# Output_eFuse.net
KiCad netlist of a schematic drawn in Altium Designer
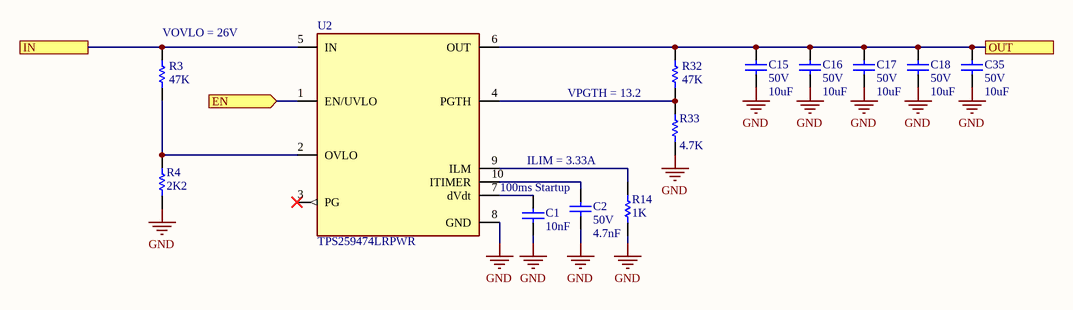
[diagram p0: Output_eFuse.SchDoc]

(export (version "E")
  (design (tool "Eeschema 10.0.6"))
  (components
    (comp (ref "C1")
      (value "CL21B103KBANNNC")
      (footprint "CAPC0805X060")
      (description "10nF ±10% 50V Ceramic Capacitor X7R 0805 (2012 Metric)")
      (fields
        (field (name "DISTRIBUTOR PART NUMBER") "C1710")
        (field (name "TOLERANCE") "10%")
        (field (name "CAPACITANCE") "10nF")
      )
      (libsource (lib "Ahristi_Library") (part "CL21B103KBANNNC"))
    )
    (comp (ref "C2")
      (value "0805B472K500NT")
      (footprint "CAPC0805X060")
      (description "4.7nF 50V X7R ±10% 0805 Multilayer Ceramic Capacitors MLCC - SMD/SMT ROHS")
      (fields
        (field (name "DISTRIBUTOR PART NUMBER") "C1744")
        (field (name "TOLERANCE") "10%")
        (field (name "VOLTAGE RATING") "50V")
        (field (name "CAPACITANCE") "4.7nF")
      )
      (libsource (lib "Ahristi_Library") (part "0805B472K500NT"))
    )
    (comp (ref "C15")
      (value "CL32B106KBJNNNE")
      (footprint "CAPC1210X090")
      (description "10 µF ±10% 50V Ceramic Capacitor X7R 1210 (3225 Metric)")
      (fields
        (field (name "DISTRIBUTOR PART NUMBER") "C138687")
        (field (name "TOLERANCE") "10%")
        (field (name "VOLTAGE RATING") "50V")
        (field (name "CAPACITANCE") "10uF")
      )
      (libsource (lib "Ahristi_Library") (part "CL32B106KBJNNNE"))
    )
    (comp (ref "C16")
      (value "CL32B106KBJNNNE")
      (footprint "CAPC1210X090")
      (description "10 µF ±10% 50V Ceramic Capacitor X7R 1210 (3225 Metric)")
      (fields
        (field (name "DISTRIBUTOR PART NUMBER") "C138687")
        (field (name "TOLERANCE") "10%")
        (field (name "VOLTAGE RATING") "50V")
        (field (name "CAPACITANCE") "10uF")
      )
      (libsource (lib "Ahristi_Library") (part "CL32B106KBJNNNE"))
    )
    (comp (ref "C17")
      (value "CL32B106KBJNNNE")
      (footprint "CAPC1210X090")
      (description "10 µF ±10% 50V Ceramic Capacitor X7R 1210 (3225 Metric)")
      (fields
        (field (name "DISTRIBUTOR PART NUMBER") "C138687")
        (field (name "TOLERANCE") "10%")
        (field (name "VOLTAGE RATING") "50V")
        (field (name "CAPACITANCE") "10uF")
      )
      (libsource (lib "Ahristi_Library") (part "CL32B106KBJNNNE"))
    )
    (comp (ref "C18")
      (value "CL32B106KBJNNNE")
      (footprint "CAPC1210X090")
      (description "10 µF ±10% 50V Ceramic Capacitor X7R 1210 (3225 Metric)")
      (fields
        (field (name "DISTRIBUTOR PART NUMBER") "C138687")
        (field (name "TOLERANCE") "10%")
        (field (name "VOLTAGE RATING") "50V")
        (field (name "CAPACITANCE") "10uF")
      )
      (libsource (lib "Ahristi_Library") (part "CL32B106KBJNNNE"))
    )
    (comp (ref "C35")
      (value "CL32B106KBJNNNE")
      (footprint "CAPC1210X090")
      (description "10 µF ±10% 50V Ceramic Capacitor X7R 1210 (3225 Metric)")
      (fields
        (field (name "DISTRIBUTOR PART NUMBER") "C138687")
        (field (name "TOLERANCE") "10%")
        (field (name "VOLTAGE RATING") "50V")
        (field (name "CAPACITANCE") "10uF")
      )
      (libsource (lib "Ahristi_Library") (part "CL32B106KBJNNNE"))
    )
    (comp (ref "R3")
      (value "0603WAF4702T5E")
      (footprint "RESC0603")
      (description "47kOhms 75V Thick Film Resistor ±1% ±100ppm/℃ 0603 Chip Resistor - Surface Mount ROHS")
      (fields
        (field (name "TOLERANCE") "1%")
        (field (name "DISTRIBUTOR PART NUMBER") "C25819")
        (field (name "RESISTANCE") "47K")
      )
      (libsource (lib "Ahristi_Library") (part "0603WAF4702T5E"))
    )
    (comp (ref "R4")
      (value "0603WAF2201T5E")
      (footprint "RESC0603")
      (description "2.2kOhms 75V Thick Film Resistor ±1% ±100ppm/℃ 0603 Chip Resistor - Surface Mount ROHS")
      (fields
        (field (name "TOLERANCE") "1%")
        (field (name "DISTRIBUTOR PART NUMBER") "C4190")
        (field (name "RESISTANCE") "2K2")
      )
      (libsource (lib "Ahristi_Library") (part "0603WAF2201T5E"))
    )
    (comp (ref "R14")
      (value "0603WAF1001T5E")
      (footprint "RESC0603")
      (description "1 kOhms 75V Thick Film Resistor ±1% ±100ppm/℃ 0603 Chip Resistor - Surface Mount ROHS")
      (fields
        (field (name "TOLERANCE") "1%")
        (field (name "DISTRIBUTOR PART NUMBER") "C21190")
        (field (name "RESISTANCE") "1K")
      )
      (libsource (lib "Ahristi_Library") (part "0603WAF1001T5E"))
    )
    (comp (ref "R32")
      (value "0603WAF4702T5E")
      (footprint "RESC0603")
      (description "47kOhms 75V Thick Film Resistor ±1% ±100ppm/℃ 0603 Chip Resistor - Surface Mount ROHS")
      (fields
        (field (name "TOLERANCE") "1%")
        (field (name "DISTRIBUTOR PART NUMBER") "C25819")
        (field (name "RESISTANCE") "47K")
      )
      (libsource (lib "Ahristi_Library") (part "0603WAF4702T5E"))
    )
    (comp (ref "R33")
      (value "0603WAF4701T5E")
      (footprint "RESC0603")
      (description "4.7 kOhms 75V Thick Film Resistor ±1% ±100ppm/℃ 0603 Chip Resistor - Surface Mount ROHS")
      (fields
        (field (name "TOLERANCE") "1%")
        (field (name "DISTRIBUTOR PART NUMBER") "C23162")
        (field (name "RESISTANCE") "4.7K")
      )
      (libsource (lib "Ahristi_Library") (part "0603WAF4701T5E"))
    )
    (comp (ref "U2")
      (value "TPS259474LRPWR")
      (footprint "VFQFN-10")
      (description "eFuse 5.5A, 2.7V~23V, 28mOhm, Reverse Current Blocking with Input Reverse Polarity Protection")
      (fields (field (name "DISTRIBUTOR PART NUMBER") "C2864845"))
      (libsource (lib "Ahristi_Library") (part "TPS259474LRPWR"))
    )
  )
  (nets
    (net (code "1") (name "/EN") (class "Default")
      (node (ref "U2") (pin "1") (pinfunction "EN/UVLO_1") (pintype "passive"))
    )
    (net (code "2") (name "/IN") (class "Default")
      (node (ref "R3") (pin "2") (pinfunction "2_2") (pintype "passive"))
      (node (ref "U2") (pin "5") (pinfunction "IN_5") (pintype "passive"))
    )
    (net (code "3") (name "/OUT") (class "Default")
      (node (ref "C15") (pin "2") (pinfunction "2_2") (pintype "passive"))
      (node (ref "C16") (pin "2") (pinfunction "2_2") (pintype "passive"))
      (node (ref "C17") (pin "2") (pinfunction "2_2") (pintype "passive"))
      (node (ref "C18") (pin "2") (pinfunction "2_2") (pintype "passive"))
      (node (ref "C35") (pin "2") (pinfunction "2_2") (pintype "passive"))
      (node (ref "R32") (pin "2") (pinfunction "2_2") (pintype "passive"))
      (node (ref "U2") (pin "6") (pinfunction "OUT_6") (pintype "passive"))
    )
    (net (code "4") (name "GND") (class "Default")
      (node (ref "C1") (pin "1") (pinfunction "1_1") (pintype "passive"))
      (node (ref "C15") (pin "1") (pinfunction "1_1") (pintype "passive"))
      (node (ref "C16") (pin "1") (pinfunction "1_1") (pintype "passive"))
      (node (ref "C17") (pin "1") (pinfunction "1_1") (pintype "passive"))
      (node (ref "C18") (pin "1") (pinfunction "1_1") (pintype "passive"))
      (node (ref "C2") (pin "1") (pinfunction "1_1") (pintype "passive"))
      (node (ref "C35") (pin "1") (pinfunction "1_1") (pintype "passive"))
      (node (ref "R14") (pin "1") (pinfunction "1_1") (pintype "passive"))
      (node (ref "R33") (pin "1") (pinfunction "1_1") (pintype "passive"))
      (node (ref "R4") (pin "1") (pinfunction "1_1") (pintype "passive"))
      (node (ref "U2") (pin "8") (pinfunction "GND_8") (pintype "passive"))
    )
    (net (code "5") (name "Net-(U2-ILM)") (class "Default")
      (node (ref "R14") (pin "2") (pinfunction "2_2") (pintype "passive"))
      (node (ref "U2") (pin "9") (pinfunction "ILM_9") (pintype "passive"))
    )
    (net (code "6") (name "Net-(U2-ITIMER)") (class "Default")
      (node (ref "C2") (pin "2") (pinfunction "2_2") (pintype "passive"))
      (node (ref "U2") (pin "10") (pinfunction "ITIMER_10") (pintype "passive"))
    )
    (net (code "7") (name "Net-(U2-OVLO)") (class "Default")
      (node (ref "R3") (pin "1") (pinfunction "1_1") (pintype "passive"))
      (node (ref "R4") (pin "2") (pinfunction "2_2") (pintype "passive"))
      (node (ref "U2") (pin "2") (pinfunction "OVLO_2") (pintype "passive"))
    )
    (net (code "8") (name "Net-(U2-PGTH)") (class "Default")
      (node (ref "R32") (pin "1") (pinfunction "1_1") (pintype "passive"))
      (node (ref "R33") (pin "2") (pinfunction "2_2") (pintype "passive"))
      (node (ref "U2") (pin "4") (pinfunction "PGTH_4") (pintype "passive"))
    )
    (net (code "9") (name "Net-(U2-dVdt)") (class "Default")
      (node (ref "C1") (pin "2") (pinfunction "2_2") (pintype "passive"))
      (node (ref "U2") (pin "7") (pinfunction "dVdt_7") (pintype "passive"))
    )
    (net (code "10") (name "unconnected-(U2-PG-Pad3)") (class "Default")
      (node (ref "U2") (pin "3") (pinfunction "PG_3") (pintype "output+no_connect"))
    )
  )
)
